# 6_DRAMBanks.net
KiCad netlist of a schematic drawn in Altium Designer
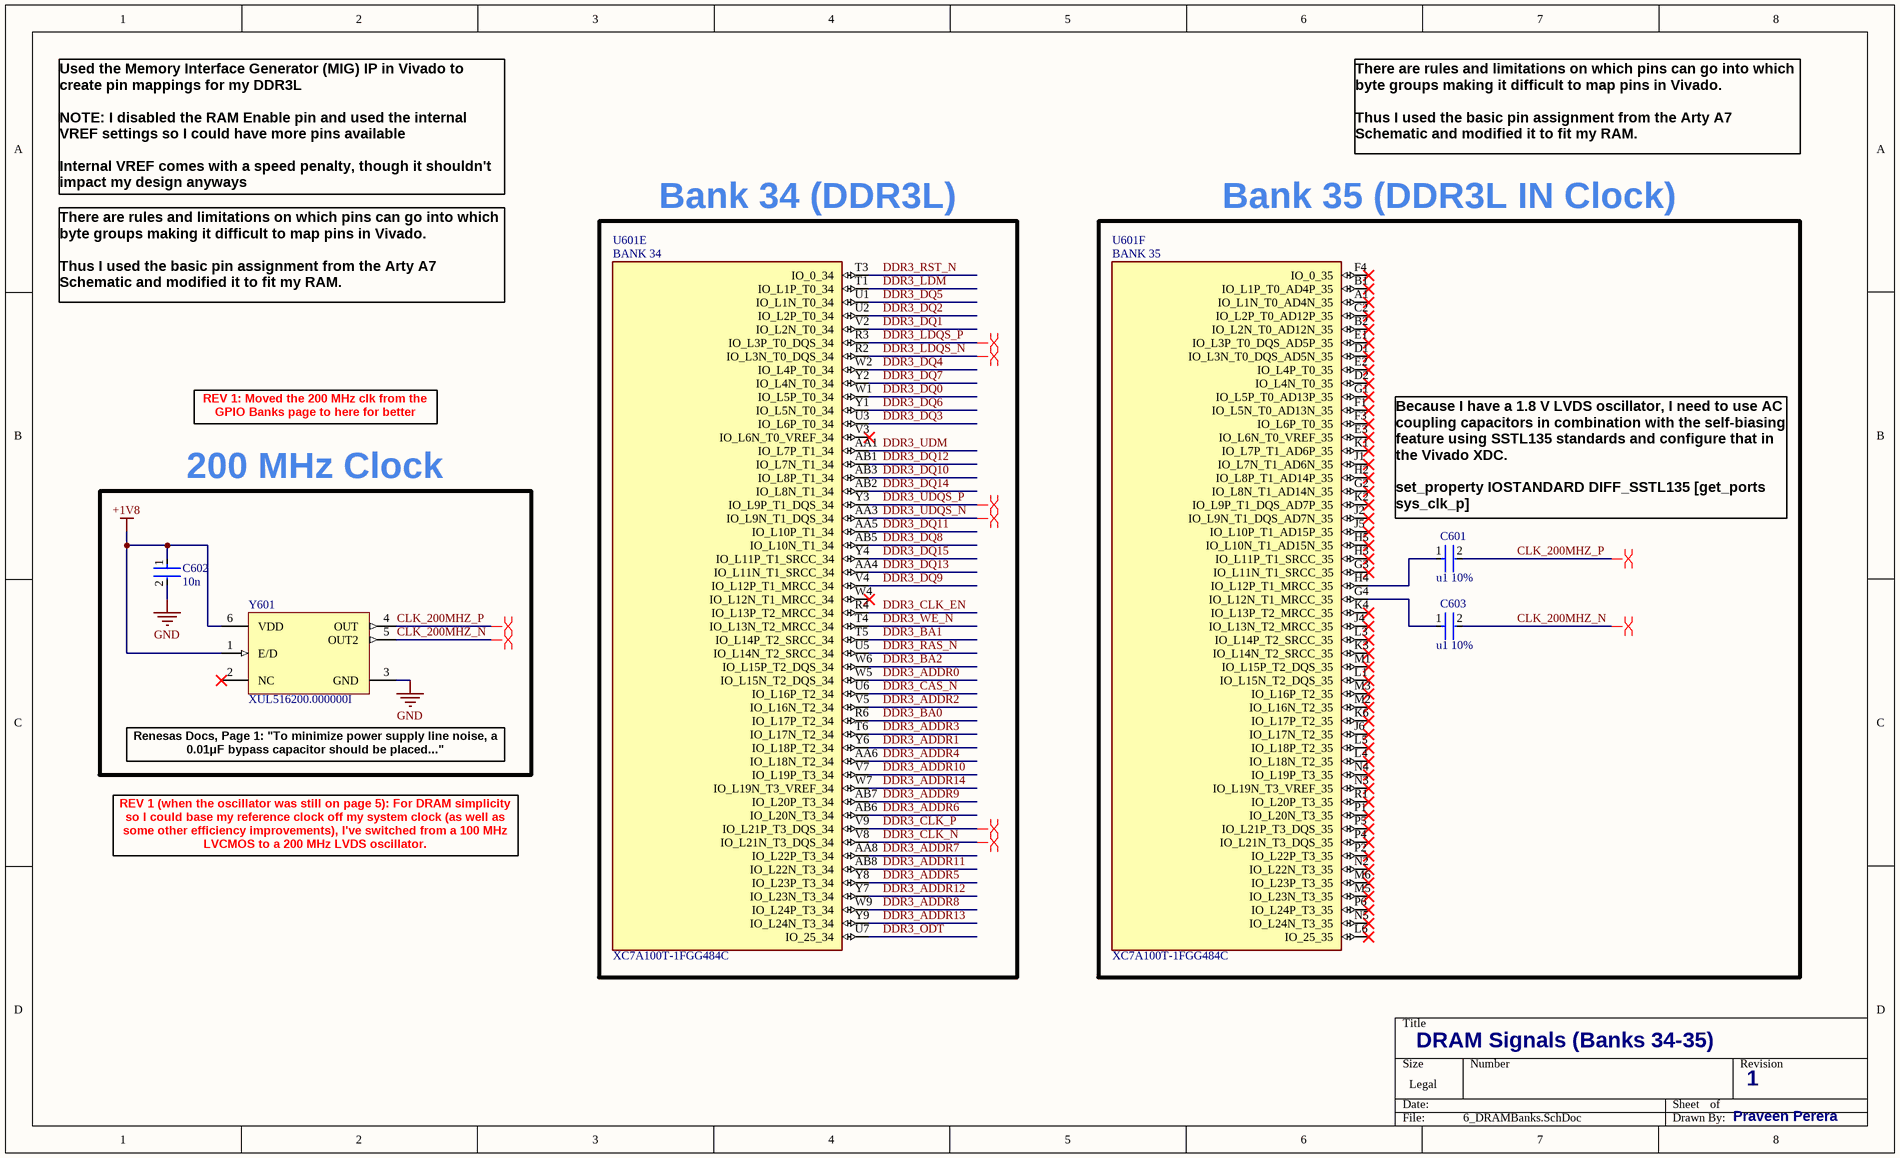
[diagram p0: 6_DRAMBanks.SchDoc]

(export (version "E")
  (design (tool "Eeschema 10.0.6"))
  (components
    (comp (ref "C601")
      (value "u1 10%")
      (footprint "FP-CL891-IPC_C")
      (description "CL05B104KB5NNNC\r\n\r\nCap Ceramic 100nF 50V X7R ±10% SMD 0402 +125°C Paper T/R")
      (libsource (lib "Altium Content Vault") (part "b4654b650e69147ec39a6b967a45e02"))
    )
    (comp (ref "C602")
      (value "10n")
      (footprint "FP-GCM155-0_05-IPC_C")
      (description "GCM155R71E103KA37D\r\n\r\nCeramic Capacitor for Automotive 10nF ±10% 25VDC X7R 0402 Paper T/R")
      (fields (field (name "VOLTAGE") "25V") (field (name "TOLERANCE") "10%"))
      (libsource (lib "Altium Content Vault") (part "02cd4be3c70576c341d710602a673aa"))
    )
    (comp (ref "C603")
      (value "u1 10%")
      (footprint "FP-CL891-IPC_C")
      (description "CL05B104KB5NNNC\r\n\r\nCap Ceramic 100nF 50V X7R ±10% SMD 0402 +125°C Paper T/R")
      (libsource (lib "Altium Content Vault") (part "b4654b650e69147ec39a6b967a45e02"))
    )
    (comp (ref "U601")
      (value "XC7A100T-1FGG484C")
      (footprint "BGA484C100P22X22_2300X2300X260N")
      (description "Artix-7 Field Programmable Gate Array (FPGA) IC 285 4976640 101440 484-BBGA")
      (fields (field (name "MF") "Xilinx Inc."))
      (libsource (lib "XC7A100T-1FGG484C - Modified") (part "XC7A100T-1FGG484C"))
    )
    (comp (ref "Y601")
      (value "XUL516200.000000I")
      (footprint "JS6_MFG")
      (description "Crystal Oscillator 200MHz LVDS 1.8VDC ±25ppm ‐40 to +85°C 4-Pin SMD 5x3.2mm Cut Tape")
      (libsource (lib "Altium Content Vault") (part "57af4c0192cbe41ed51f7d5823f7c83"))
    )
  )
  (nets
    (net (code "1") (name "+1V8") (class "Default")
      (node (ref "C602") (pin "1") (pinfunction "1_1") (pintype "passive"))
      (node (ref "Y601") (pin "1") (pinfunction "E/D_1") (pintype "input"))
      (node (ref "Y601") (pin "6") (pinfunction "VDD_6") (pintype "power_in"))
    )
    (net (code "2") (name "/CLK_200MHZ_N") (class "Default")
      (node (ref "C603") (pin "2") (pinfunction "2_2") (pintype "passive"))
      (node (ref "Y601") (pin "5") (pinfunction "OUT2_5") (pintype "output"))
    )
    (net (code "3") (name "/CLK_200MHZ_P") (class "Default")
      (node (ref "C601") (pin "2") (pinfunction "2_2") (pintype "passive"))
      (node (ref "Y601") (pin "4") (pinfunction "OUT_4") (pintype "output"))
    )
    (net (code "4") (name "/DDR3_ADDR0") (class "Default")
      (node (ref "U601") (pin "W5") (pinfunction "IO_L15N_T2_DQS_34_W5") (pintype "bidirectional"))
    )
    (net (code "5") (name "/DDR3_ADDR1") (class "Default")
      (node (ref "U601") (pin "Y6") (pinfunction "IO_L18P_T2_34_Y6") (pintype "bidirectional"))
    )
    (net (code "6") (name "/DDR3_ADDR2") (class "Default")
      (node (ref "U601") (pin "V5") (pinfunction "IO_L16N_T2_34_V5") (pintype "bidirectional"))
    )
    (net (code "7") (name "/DDR3_ADDR3") (class "Default")
      (node (ref "U601") (pin "T6") (pinfunction "IO_L17N_T2_34_T6") (pintype "bidirectional"))
    )
    (net (code "8") (name "/DDR3_ADDR4") (class "Default")
      (node (ref "U601") (pin "AA6") (pinfunction "IO_L18N_T2_34_AA6") (pintype "bidirectional"))
    )
    (net (code "9") (name "/DDR3_ADDR5") (class "Default")
      (node (ref "U601") (pin "Y8") (pinfunction "IO_L23P_T3_34_Y8") (pintype "bidirectional"))
    )
    (net (code "10") (name "/DDR3_ADDR6") (class "Default")
      (node (ref "U601") (pin "AB6") (pinfunction "IO_L20N_T3_34_AB6") (pintype "bidirectional"))
    )
    (net (code "11") (name "/DDR3_ADDR7") (class "Default")
      (node (ref "U601") (pin "AA8") (pinfunction "IO_L22P_T3_34_AA8") (pintype "bidirectional"))
    )
    (net (code "12") (name "/DDR3_ADDR8") (class "Default")
      (node (ref "U601") (pin "W9") (pinfunction "IO_L24P_T3_34_W9") (pintype "bidirectional"))
    )
    (net (code "13") (name "/DDR3_ADDR9") (class "Default")
      (node (ref "U601") (pin "AB7") (pinfunction "IO_L20P_T3_34_AB7") (pintype "bidirectional"))
    )
    (net (code "14") (name "/DDR3_ADDR10") (class "Default")
      (node (ref "U601") (pin "V7") (pinfunction "IO_L19P_T3_34_V7") (pintype "bidirectional"))
    )
    (net (code "15") (name "/DDR3_ADDR11") (class "Default")
      (node (ref "U601") (pin "AB8") (pinfunction "IO_L22N_T3_34_AB8") (pintype "bidirectional"))
    )
    (net (code "16") (name "/DDR3_ADDR12") (class "Default")
      (node (ref "U601") (pin "Y7") (pinfunction "IO_L23N_T3_34_Y7") (pintype "bidirectional"))
    )
    (net (code "17") (name "/DDR3_ADDR13") (class "Default")
      (node (ref "U601") (pin "Y9") (pinfunction "IO_L24N_T3_34_Y9") (pintype "bidirectional"))
    )
    (net (code "18") (name "/DDR3_ADDR14") (class "Default")
      (node (ref "U601") (pin "W7") (pinfunction "IO_L19N_T3_VREF_34_W7") (pintype "bidirectional"))
    )
    (net (code "19") (name "/DDR3_BA0") (class "Default")
      (node (ref "U601") (pin "R6") (pinfunction "IO_L17P_T2_34_R6") (pintype "bidirectional"))
    )
    (net (code "20") (name "/DDR3_BA1") (class "Default")
      (node (ref "U601") (pin "T5") (pinfunction "IO_L14P_T2_SRCC_34_T5") (pintype "bidirectional"))
    )
    (net (code "21") (name "/DDR3_BA2") (class "Default")
      (node (ref "U601") (pin "W6") (pinfunction "IO_L15P_T2_DQS_34_W6") (pintype "bidirectional"))
    )
    (net (code "22") (name "/DDR3_CAS_N") (class "Default")
      (node (ref "U601") (pin "U6") (pinfunction "IO_L16P_T2_34_U6") (pintype "bidirectional"))
    )
    (net (code "23") (name "/DDR3_CLK_EN") (class "Default")
      (node (ref "U601") (pin "R4") (pinfunction "IO_L13P_T2_MRCC_34_R4") (pintype "bidirectional"))
    )
    (net (code "24") (name "/DDR3_CLK_N") (class "Default")
      (node (ref "U601") (pin "V8") (pinfunction "IO_L21N_T3_DQS_34_V8") (pintype "bidirectional"))
    )
    (net (code "25") (name "/DDR3_CLK_P") (class "Default")
      (node (ref "U601") (pin "V9") (pinfunction "IO_L21P_T3_DQS_34_V9") (pintype "bidirectional"))
    )
    (net (code "26") (name "/DDR3_DQ0") (class "Default")
      (node (ref "U601") (pin "W1") (pinfunction "IO_L5P_T0_34_W1") (pintype "bidirectional"))
    )
    (net (code "27") (name "/DDR3_DQ1") (class "Default")
      (node (ref "U601") (pin "V2") (pinfunction "IO_L2N_T0_34_V2") (pintype "bidirectional"))
    )
    (net (code "28") (name "/DDR3_DQ2") (class "Default")
      (node (ref "U601") (pin "U2") (pinfunction "IO_L2P_T0_34_U2") (pintype "bidirectional"))
    )
    (net (code "29") (name "/DDR3_DQ3") (class "Default")
      (node (ref "U601") (pin "U3") (pinfunction "IO_L6P_T0_34_U3") (pintype "bidirectional"))
    )
    (net (code "30") (name "/DDR3_DQ4") (class "Default")
      (node (ref "U601") (pin "W2") (pinfunction "IO_L4P_T0_34_W2") (pintype "bidirectional"))
    )
    (net (code "31") (name "/DDR3_DQ5") (class "Default")
      (node (ref "U601") (pin "U1") (pinfunction "IO_L1N_T0_34_U1") (pintype "bidirectional"))
    )
    (net (code "32") (name "/DDR3_DQ6") (class "Default")
      (node (ref "U601") (pin "Y1") (pinfunction "IO_L5N_T0_34_Y1") (pintype "bidirectional"))
    )
    (net (code "33") (name "/DDR3_DQ7") (class "Default")
      (node (ref "U601") (pin "Y2") (pinfunction "IO_L4N_T0_34_Y2") (pintype "bidirectional"))
    )
    (net (code "34") (name "/DDR3_DQ8") (class "Default")
      (node (ref "U601") (pin "AB5") (pinfunction "IO_L10N_T1_34_AB5") (pintype "bidirectional"))
    )
    (net (code "35") (name "/DDR3_DQ9") (class "Default")
      (node (ref "U601") (pin "V4") (pinfunction "IO_L12P_T1_MRCC_34_V4") (pintype "bidirectional"))
    )
    (net (code "36") (name "/DDR3_DQ10") (class "Default")
      (node (ref "U601") (pin "AB3") (pinfunction "IO_L8P_T1_34_AB3") (pintype "bidirectional"))
    )
    (net (code "37") (name "/DDR3_DQ11") (class "Default")
      (node (ref "U601") (pin "AA5") (pinfunction "IO_L10P_T1_34_AA5") (pintype "bidirectional"))
    )
    (net (code "38") (name "/DDR3_DQ12") (class "Default")
      (node (ref "U601") (pin "AB1") (pinfunction "IO_L7N_T1_34_AB1") (pintype "bidirectional"))
    )
    (net (code "39") (name "/DDR3_DQ13") (class "Default")
      (node (ref "U601") (pin "AA4") (pinfunction "IO_L11N_T1_SRCC_34_AA4") (pintype "bidirectional"))
    )
    (net (code "40") (name "/DDR3_DQ14") (class "Default")
      (node (ref "U601") (pin "AB2") (pinfunction "IO_L8N_T1_34_AB2") (pintype "bidirectional"))
    )
    (net (code "41") (name "/DDR3_DQ15") (class "Default")
      (node (ref "U601") (pin "Y4") (pinfunction "IO_L11P_T1_SRCC_34_Y4") (pintype "bidirectional"))
    )
    (net (code "42") (name "/DDR3_LDM") (class "Default")
      (node (ref "U601") (pin "T1") (pinfunction "IO_L1P_T0_34_T1") (pintype "bidirectional"))
    )
    (net (code "43") (name "/DDR3_LDQS_N") (class "Default")
      (node (ref "U601") (pin "R2") (pinfunction "IO_L3N_T0_DQS_34_R2") (pintype "bidirectional"))
    )
    (net (code "44") (name "/DDR3_LDQS_P") (class "Default")
      (node (ref "U601") (pin "R3") (pinfunction "IO_L3P_T0_DQS_34_R3") (pintype "bidirectional"))
    )
    (net (code "45") (name "/DDR3_ODT") (class "Default")
      (node (ref "U601") (pin "U7") (pinfunction "IO_25_34_U7") (pintype "bidirectional"))
    )
    (net (code "46") (name "/DDR3_RAS_N") (class "Default")
      (node (ref "U601") (pin "U5") (pinfunction "IO_L14N_T2_SRCC_34_U5") (pintype "bidirectional"))
    )
    (net (code "47") (name "/DDR3_RST_N") (class "Default")
      (node (ref "U601") (pin "T3") (pinfunction "IO_0_34_T3") (pintype "bidirectional"))
    )
    (net (code "48") (name "/DDR3_UDM") (class "Default")
      (node (ref "U601") (pin "AA1") (pinfunction "IO_L7P_T1_34_AA1") (pintype "bidirectional"))
    )
    (net (code "49") (name "/DDR3_UDQS_N") (class "Default")
      (node (ref "U601") (pin "AA3") (pinfunction "IO_L9N_T1_DQS_34_AA3") (pintype "bidirectional"))
    )
    (net (code "50") (name "/DDR3_UDQS_P") (class "Default")
      (node (ref "U601") (pin "Y3") (pinfunction "IO_L9P_T1_DQS_34_Y3") (pintype "bidirectional"))
    )
    (net (code "51") (name "/DDR3_WE_N") (class "Default")
      (node (ref "U601") (pin "T4") (pinfunction "IO_L13N_T2_MRCC_34_T4") (pintype "bidirectional"))
    )
    (net (code "52") (name "GND") (class "Default")
      (node (ref "C602") (pin "2") (pinfunction "2_2") (pintype "passive"))
      (node (ref "Y601") (pin "3") (pinfunction "GND_3") (pintype "power_in"))
    )
    (net (code "53") (name "Net-(U601F-IO_L12N_T1_MRCC_35)") (class "Default")
      (node (ref "C603") (pin "1") (pinfunction "1_1") (pintype "passive"))
      (node (ref "U601") (pin "G4") (pinfunction "IO_L12N_T1_MRCC_35_G4") (pintype "bidirectional"))
    )
    (net (code "54") (name "Net-(U601F-IO_L12P_T1_MRCC_35)") (class "Default")
      (node (ref "C601") (pin "1") (pinfunction "1_1") (pintype "passive"))
      (node (ref "U601") (pin "H4") (pinfunction "IO_L12P_T1_MRCC_35_H4") (pintype "bidirectional"))
    )
    (net (code "55") (name "unconnected-(U601E-IO_L6N_T0_VREF_34-PadV3)") (class "Default")
      (node (ref "U601") (pin "V3") (pinfunction "IO_L6N_T0_VREF_34_V3") (pintype "bidirectional+no_connect"))
    )
    (net (code "56") (name "unconnected-(U601E-IO_L12N_T1_MRCC_34-PadW4)") (class "Default")
      (node (ref "U601") (pin "W4") (pinfunction "IO_L12N_T1_MRCC_34_W4") (pintype "bidirectional+no_connect"))
    )
    (net (code "57") (name "unconnected-(U601F-IO_0_35-PadF4)") (class "Default")
      (node (ref "U601") (pin "F4") (pinfunction "IO_0_35_F4") (pintype "bidirectional+no_connect"))
    )
    (net (code "58") (name "unconnected-(U601F-IO_25_35-PadL6)") (class "Default")
      (node (ref "U601") (pin "L6") (pinfunction "IO_25_35_L6") (pintype "bidirectional+no_connect"))
    )
    (net (code "59") (name "unconnected-(U601F-IO_L1N_T0_AD4N_35-PadA1)") (class "Default")
      (node (ref "U601") (pin "A1") (pinfunction "IO_L1N_T0_AD4N_35_A1") (pintype "bidirectional+no_connect"))
    )
    (net (code "60") (name "unconnected-(U601F-IO_L1P_T0_AD4P_35-PadB1)") (class "Default")
      (node (ref "U601") (pin "B1") (pinfunction "IO_L1P_T0_AD4P_35_B1") (pintype "bidirectional+no_connect"))
    )
    (net (code "61") (name "unconnected-(U601F-IO_L2N_T0_AD12N_35-PadB2)") (class "Default")
      (node (ref "U601") (pin "B2") (pinfunction "IO_L2N_T0_AD12N_35_B2") (pintype "bidirectional+no_connect"))
    )
    (net (code "62") (name "unconnected-(U601F-IO_L2P_T0_AD12P_35-PadC2)") (class "Default")
      (node (ref "U601") (pin "C2") (pinfunction "IO_L2P_T0_AD12P_35_C2") (pintype "bidirectional+no_connect"))
    )
    (net (code "63") (name "unconnected-(U601F-IO_L3N_T0_DQS_AD5N_35-PadD1)") (class "Default")
      (node (ref "U601") (pin "D1") (pinfunction "IO_L3N_T0_DQS_AD5N_35_D1") (pintype "bidirectional+no_connect"))
    )
    (net (code "64") (name "unconnected-(U601F-IO_L3P_T0_DQS_AD5P_35-PadE1)") (class "Default")
      (node (ref "U601") (pin "E1") (pinfunction "IO_L3P_T0_DQS_AD5P_35_E1") (pintype "bidirectional+no_connect"))
    )
    (net (code "65") (name "unconnected-(U601F-IO_L4N_T0_35-PadD2)") (class "Default")
      (node (ref "U601") (pin "D2") (pinfunction "IO_L4N_T0_35_D2") (pintype "bidirectional+no_connect"))
    )
    (net (code "66") (name "unconnected-(U601F-IO_L4P_T0_35-PadE2)") (class "Default")
      (node (ref "U601") (pin "E2") (pinfunction "IO_L4P_T0_35_E2") (pintype "bidirectional+no_connect"))
    )
    (net (code "67") (name "unconnected-(U601F-IO_L5N_T0_AD13N_35-PadF1)") (class "Default")
      (node (ref "U601") (pin "F1") (pinfunction "IO_L5N_T0_AD13N_35_F1") (pintype "bidirectional+no_connect"))
    )
    (net (code "68") (name "unconnected-(U601F-IO_L5P_T0_AD13P_35-PadG1)") (class "Default")
      (node (ref "U601") (pin "G1") (pinfunction "IO_L5P_T0_AD13P_35_G1") (pintype "bidirectional+no_connect"))
    )
    (net (code "69") (name "unconnected-(U601F-IO_L6N_T0_VREF_35-PadE3)") (class "Default")
      (node (ref "U601") (pin "E3") (pinfunction "IO_L6N_T0_VREF_35_E3") (pintype "bidirectional+no_connect"))
    )
    (net (code "70") (name "unconnected-(U601F-IO_L6P_T0_35-PadF3)") (class "Default")
      (node (ref "U601") (pin "F3") (pinfunction "IO_L6P_T0_35_F3") (pintype "bidirectional+no_connect"))
    )
    (net (code "71") (name "unconnected-(U601F-IO_L7N_T1_AD6N_35-PadJ1)") (class "Default")
      (node (ref "U601") (pin "J1") (pinfunction "IO_L7N_T1_AD6N_35_J1") (pintype "bidirectional+no_connect"))
    )
    (net (code "72") (name "unconnected-(U601F-IO_L7P_T1_AD6P_35-PadK1)") (class "Default")
      (node (ref "U601") (pin "K1") (pinfunction "IO_L7P_T1_AD6P_35_K1") (pintype "bidirectional+no_connect"))
    )
    (net (code "73") (name "unconnected-(U601F-IO_L8N_T1_AD14N_35-PadG2)") (class "Default")
      (node (ref "U601") (pin "G2") (pinfunction "IO_L8N_T1_AD14N_35_G2") (pintype "bidirectional+no_connect"))
    )
    (net (code "74") (name "unconnected-(U601F-IO_L8P_T1_AD14P_35-PadH2)") (class "Default")
      (node (ref "U601") (pin "H2") (pinfunction "IO_L8P_T1_AD14P_35_H2") (pintype "bidirectional+no_connect"))
    )
    (net (code "75") (name "unconnected-(U601F-IO_L9N_T1_DQS_AD7N_35-PadJ2)") (class "Default")
      (node (ref "U601") (pin "J2") (pinfunction "IO_L9N_T1_DQS_AD7N_35_J2") (pintype "bidirectional+no_connect"))
    )
    (net (code "76") (name "unconnected-(U601F-IO_L9P_T1_DQS_AD7P_35-PadK2)") (class "Default")
      (node (ref "U601") (pin "K2") (pinfunction "IO_L9P_T1_DQS_AD7P_35_K2") (pintype "bidirectional+no_connect"))
    )
    (net (code "77") (name "unconnected-(U601F-IO_L10N_T1_AD15N_35-PadH5)") (class "Default")
      (node (ref "U601") (pin "H5") (pinfunction "IO_L10N_T1_AD15N_35_H5") (pintype "bidirectional+no_connect"))
    )
    (net (code "78") (name "unconnected-(U601F-IO_L10P_T1_AD15P_35-PadJ5)") (class "Default")
      (node (ref "U601") (pin "J5") (pinfunction "IO_L10P_T1_AD15P_35_J5") (pintype "bidirectional+no_connect"))
    )
    (net (code "79") (name "unconnected-(U601F-IO_L11N_T1_SRCC_35-PadG3)") (class "Default")
      (node (ref "U601") (pin "G3") (pinfunction "IO_L11N_T1_SRCC_35_G3") (pintype "bidirectional+no_connect"))
    )
    (net (code "80") (name "unconnected-(U601F-IO_L11P_T1_SRCC_35-PadH3)") (class "Default")
      (node (ref "U601") (pin "H3") (pinfunction "IO_L11P_T1_SRCC_35_H3") (pintype "bidirectional+no_connect"))
    )
    (net (code "81") (name "unconnected-(U601F-IO_L13N_T2_MRCC_35-PadJ4)") (class "Default")
      (node (ref "U601") (pin "J4") (pinfunction "IO_L13N_T2_MRCC_35_J4") (pintype "bidirectional+no_connect"))
    )
    (net (code "82") (name "unconnected-(U601F-IO_L13P_T2_MRCC_35-PadK4)") (class "Default")
      (node (ref "U601") (pin "K4") (pinfunction "IO_L13P_T2_MRCC_35_K4") (pintype "bidirectional+no_connect"))
    )
    (net (code "83") (name "unconnected-(U601F-IO_L14N_T2_SRCC_35-PadK3)") (class "Default")
      (node (ref "U601") (pin "K3") (pinfunction "IO_L14N_T2_SRCC_35_K3") (pintype "bidirectional+no_connect"))
    )
    (net (code "84") (name "unconnected-(U601F-IO_L14P_T2_SRCC_35-PadL3)") (class "Default")
      (node (ref "U601") (pin "L3") (pinfunction "IO_L14P_T2_SRCC_35_L3") (pintype "bidirectional+no_connect"))
    )
    (net (code "85") (name "unconnected-(U601F-IO_L15N_T2_DQS_35-PadL1)") (class "Default")
      (node (ref "U601") (pin "L1") (pinfunction "IO_L15N_T2_DQS_35_L1") (pintype "bidirectional+no_connect"))
    )
    (net (code "86") (name "unconnected-(U601F-IO_L15P_T2_DQS_35-PadM1)") (class "Default")
      (node (ref "U601") (pin "M1") (pinfunction "IO_L15P_T2_DQS_35_M1") (pintype "bidirectional+no_connect"))
    )
    (net (code "87") (name "unconnected-(U601F-IO_L16N_T2_35-PadM2)") (class "Default")
      (node (ref "U601") (pin "M2") (pinfunction "IO_L16N_T2_35_M2") (pintype "bidirectional+no_connect"))
    )
    (net (code "88") (name "unconnected-(U601F-IO_L16P_T2_35-PadM3)") (class "Default")
      (node (ref "U601") (pin "M3") (pinfunction "IO_L16P_T2_35_M3") (pintype "bidirectional+no_connect"))
    )
    (net (code "89") (name "unconnected-(U601F-IO_L17N_T2_35-PadJ6)") (class "Default")
      (node (ref "U601") (pin "J6") (pinfunction "IO_L17N_T2_35_J6") (pintype "bidirectional+no_connect"))
    )
    (net (code "90") (name "unconnected-(U601F-IO_L17P_T2_35-PadK6)") (class "Default")
      (node (ref "U601") (pin "K6") (pinfunction "IO_L17P_T2_35_K6") (pintype "bidirectional+no_connect"))
    )
    (net (code "91") (name "unconnected-(U601F-IO_L18N_T2_35-PadL4)") (class "Default")
      (node (ref "U601") (pin "L4") (pinfunction "IO_L18N_T2_35_L4") (pintype "bidirectional+no_connect"))
    )
    (net (code "92") (name "unconnected-(U601F-IO_L18P_T2_35-PadL5)") (class "Default")
      (node (ref "U601") (pin "L5") (pinfunction "IO_L18P_T2_35_L5") (pintype "bidirectional+no_connect"))
    )
    (net (code "93") (name "unconnected-(U601F-IO_L19N_T3_VREF_35-PadN3)") (class "Default")
      (node (ref "U601") (pin "N3") (pinfunction "IO_L19N_T3_VREF_35_N3") (pintype "bidirectional+no_connect"))
    )
    (net (code "94") (name "unconnected-(U601F-IO_L19P_T3_35-PadN4)") (class "Default")
      (node (ref "U601") (pin "N4") (pinfunction "IO_L19P_T3_35_N4") (pintype "bidirectional+no_connect"))
    )
    (net (code "95") (name "unconnected-(U601F-IO_L20N_T3_35-PadP1)") (class "Default")
      (node (ref "U601") (pin "P1") (pinfunction "IO_L20N_T3_35_P1") (pintype "bidirectional+no_connect"))
    )
    (net (code "96") (name "unconnected-(U601F-IO_L20P_T3_35-PadR1)") (class "Default")
      (node (ref "U601") (pin "R1") (pinfunction "IO_L20P_T3_35_R1") (pintype "bidirectional+no_connect"))
    )
    (net (code "97") (name "unconnected-(U601F-IO_L21N_T3_DQS_35-PadP4)") (class "Default")
      (node (ref "U601") (pin "P4") (pinfunction "IO_L21N_T3_DQS_35_P4") (pintype "bidirectional+no_connect"))
    )
    (net (code "98") (name "unconnected-(U601F-IO_L21P_T3_DQS_35-PadP5)") (class "Default")
      (node (ref "U601") (pin "P5") (pinfunction "IO_L21P_T3_DQS_35_P5") (pintype "bidirectional+no_connect"))
    )
    (net (code "99") (name "unconnected-(U601F-IO_L22N_T3_35-PadN2)") (class "Default")
      (node (ref "U601") (pin "N2") (pinfunction "IO_L22N_T3_35_N2") (pintype "bidirectional+no_connect"))
    )
    (net (code "100") (name "unconnected-(U601F-IO_L22P_T3_35-PadP2)") (class "Default")
      (node (ref "U601") (pin "P2") (pinfunction "IO_L22P_T3_35_P2") (pintype "bidirectional+no_connect"))
    )
    (net (code "101") (name "unconnected-(U601F-IO_L23N_T3_35-PadM5)") (class "Default")
      (node (ref "U601") (pin "M5") (pinfunction "IO_L23N_T3_35_M5") (pintype "bidirectional+no_connect"))
    )
    (net (code "102") (name "unconnected-(U601F-IO_L23P_T3_35-PadM6)") (class "Default")
      (node (ref "U601") (pin "M6") (pinfunction "IO_L23P_T3_35_M6") (pintype "bidirectional+no_connect"))
    )
    (net (code "103") (name "unconnected-(U601F-IO_L24N_T3_35-PadN5)") (class "Default")
      (node (ref "U601") (pin "N5") (pinfunction "IO_L24N_T3_35_N5") (pintype "bidirectional+no_connect"))
    )
    (net (code "104") (name "unconnected-(U601F-IO_L24P_T3_35-PadP6)") (class "Default")
      (node (ref "U601") (pin "P6") (pinfunction "IO_L24P_T3_35_P6") (pintype "bidirectional+no_connect"))
    )
    (net (code "105") (name "unconnected-(Y601-NC-Pad2)") (class "Default")
      (node (ref "Y601") (pin "2") (pinfunction "NC_2") (pintype "passive+no_connect"))
    )
  )
)
